# Indicators.net
KiCad netlist of a schematic drawn in Altium Designer
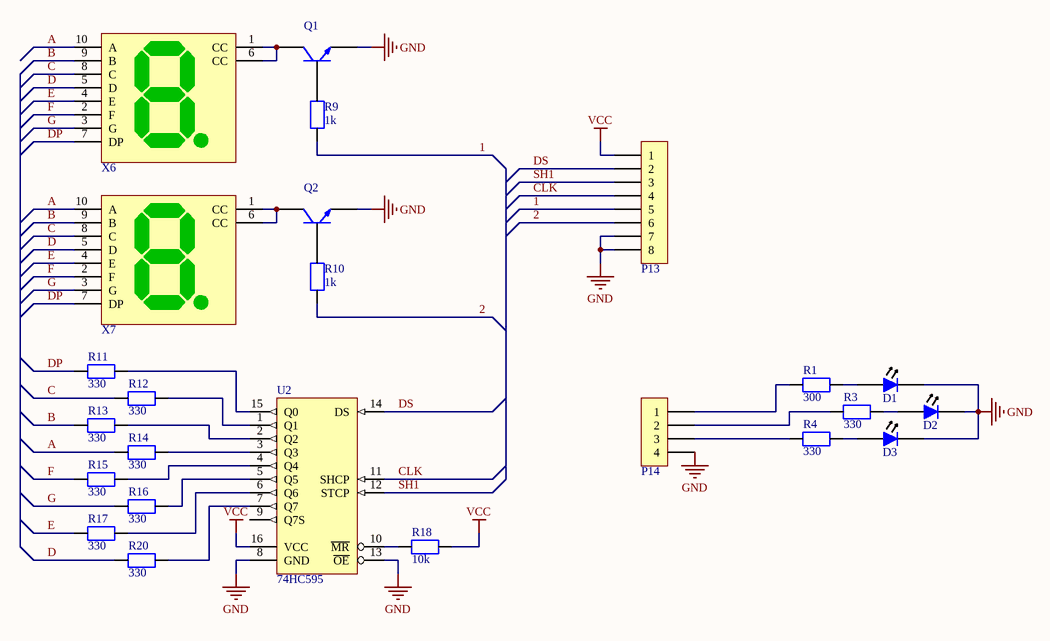
[diagram p0: Indicators.SchDoc]

(export (version "E")
  (design (tool "Eeschema 10.0.6"))
  (components
    (comp (ref "D1") (value "LED") (footprint "LED") (libsource (lib "SchLib1") (part "LED")))
    (comp (ref "D2") (value "LED") (footprint "LED") (libsource (lib "SchLib1") (part "LED")))
    (comp (ref "D3") (value "LED") (footprint "LED") (libsource (lib "SchLib1") (part "LED")))
    (comp (ref "P13")
      (value "SIL-CONN-8")
      (footprint "SIL-CONN-8-R1")
      (libsource (lib "SchLib1") (part "SIL-CONN-8"))
    )
    (comp (ref "P14")
      (value "SIL-CONN-4")
      (footprint "SIL-CONN-4-R1")
      (libsource (lib "SchLib1") (part "SIL-CONN-4"))
    )
    (comp (ref "Q1") (value "KT315") (footprint "KT315") (libsource (lib "SchLib1") (part "KT315")))
    (comp (ref "Q2") (value "KT315") (footprint "KT315") (libsource (lib "SchLib1") (part "KT315")))
    (comp (ref "R1")
      (value "300")
      (footprint "0805_Resistor")
      (fields (field (name "Comment") "Resistor"))
      (libsource (lib "SchLib1") (part "Resistor"))
    )
    (comp (ref "R3")
      (value "330")
      (footprint "0805_Resistor")
      (fields (field (name "Comment") "Resistor"))
      (libsource (lib "SchLib1") (part "Resistor"))
    )
    (comp (ref "R4")
      (value "330")
      (footprint "0805_Resistor")
      (fields (field (name "Comment") "Resistor"))
      (libsource (lib "SchLib1") (part "Resistor"))
    )
    (comp (ref "R9")
      (value "1k")
      (footprint "0805_Resistor")
      (fields (field (name "Comment") "Resistor"))
      (libsource (lib "") (part "Resistor_1"))
    )
    (comp (ref "R10")
      (value "1k")
      (footprint "0805_Resistor")
      (fields (field (name "Comment") "Resistor"))
      (libsource (lib "") (part "Resistor_1"))
    )
    (comp (ref "R11")
      (value "330")
      (footprint "0805_Resistor")
      (fields (field (name "Comment") "Resistor"))
      (libsource (lib "SchLib1") (part "Resistor"))
    )
    (comp (ref "R12")
      (value "330")
      (footprint "0805_Resistor")
      (fields (field (name "Comment") "Resistor"))
      (libsource (lib "SchLib1") (part "Resistor"))
    )
    (comp (ref "R13")
      (value "330")
      (footprint "0805_Resistor")
      (fields (field (name "Comment") "Resistor"))
      (libsource (lib "SchLib1") (part "Resistor"))
    )
    (comp (ref "R14")
      (value "330")
      (footprint "0805_Resistor")
      (fields (field (name "Comment") "Resistor"))
      (libsource (lib "SchLib1") (part "Resistor"))
    )
    (comp (ref "R15")
      (value "330")
      (footprint "0805_Resistor")
      (fields (field (name "Comment") "Resistor"))
      (libsource (lib "SchLib1") (part "Resistor"))
    )
    (comp (ref "R16")
      (value "330")
      (footprint "0805_Resistor")
      (fields (field (name "Comment") "Resistor"))
      (libsource (lib "SchLib1") (part "Resistor"))
    )
    (comp (ref "R17")
      (value "330")
      (footprint "0805_Resistor")
      (fields (field (name "Comment") "Resistor"))
      (libsource (lib "SchLib1") (part "Resistor"))
    )
    (comp (ref "R18")
      (value "10k")
      (footprint "0805_Resistor")
      (fields (field (name "Comment") "Resistor"))
      (libsource (lib "SchLib1") (part "Resistor"))
    )
    (comp (ref "R20")
      (value "330")
      (footprint "0805_Resistor")
      (fields (field (name "Comment") "Resistor"))
      (libsource (lib "SchLib1") (part "Resistor"))
    )
    (comp (ref "U2") (value "74HC595") (footprint "SOIC16") (libsource (lib "SchLib1") (part "74HC595")))
    (comp (ref "X6") (value "FYS-3912") (footprint "FYS-3916") (libsource (lib "SchLib1") (part "FYS-3912")))
    (comp (ref "X7") (value "FYS-3912") (footprint "FYS-3916") (libsource (lib "SchLib1") (part "FYS-3912")))
  )
  (nets
    (net (code "1") (name "/1") (class "Default")
      (node (ref "P13") (pin "5") (pinfunction "5_5") (pintype "passive"))
      (node (ref "R9") (pin "1") (pinfunction "1_1") (pintype "passive"))
    )
    (net (code "2") (name "/2") (class "Default")
      (node (ref "P13") (pin "6") (pinfunction "6_6") (pintype "passive"))
      (node (ref "R10") (pin "1") (pinfunction "1_1") (pintype "passive"))
    )
    (net (code "3") (name "/A") (class "Default")
      (node (ref "R14") (pin "2") (pinfunction "2_2") (pintype "passive"))
      (node (ref "X6") (pin "10") (pinfunction "A_10") (pintype "passive"))
      (node (ref "X7") (pin "10") (pinfunction "A_10") (pintype "passive"))
    )
    (net (code "4") (name "/B") (class "Default")
      (node (ref "R13") (pin "2") (pinfunction "2_2") (pintype "passive"))
      (node (ref "X6") (pin "9") (pinfunction "B_9") (pintype "passive"))
      (node (ref "X7") (pin "9") (pinfunction "B_9") (pintype "passive"))
    )
    (net (code "5") (name "/C") (class "Default")
      (node (ref "R12") (pin "2") (pinfunction "2_2") (pintype "passive"))
      (node (ref "X6") (pin "8") (pinfunction "C_8") (pintype "passive"))
      (node (ref "X7") (pin "8") (pinfunction "C_8") (pintype "passive"))
    )
    (net (code "6") (name "/CLK") (class "Default")
      (node (ref "P13") (pin "4") (pinfunction "4_4") (pintype "passive"))
      (node (ref "U2") (pin "11") (pinfunction "SHCP_11") (pintype "input"))
    )
    (net (code "7") (name "/D") (class "Default")
      (node (ref "R20") (pin "2") (pinfunction "2_2") (pintype "passive"))
      (node (ref "X6") (pin "5") (pinfunction "D_5") (pintype "passive"))
      (node (ref "X7") (pin "5") (pinfunction "D_5") (pintype "passive"))
    )
    (net (code "8") (name "/DP") (class "Default")
      (node (ref "R11") (pin "2") (pinfunction "2_2") (pintype "passive"))
      (node (ref "X6") (pin "7") (pinfunction "DP_7") (pintype "passive"))
      (node (ref "X7") (pin "7") (pinfunction "DP_7") (pintype "passive"))
    )
    (net (code "9") (name "/DS") (class "Default")
      (node (ref "P13") (pin "2") (pinfunction "2_2") (pintype "passive"))
      (node (ref "U2") (pin "14") (pinfunction "DS_14") (pintype "input"))
    )
    (net (code "10") (name "/E") (class "Default")
      (node (ref "R17") (pin "2") (pinfunction "2_2") (pintype "passive"))
      (node (ref "X6") (pin "4") (pinfunction "E_4") (pintype "passive"))
      (node (ref "X7") (pin "4") (pinfunction "E_4") (pintype "passive"))
    )
    (net (code "11") (name "/F") (class "Default")
      (node (ref "R15") (pin "2") (pinfunction "2_2") (pintype "passive"))
      (node (ref "X6") (pin "2") (pinfunction "F_2") (pintype "passive"))
      (node (ref "X7") (pin "2") (pinfunction "F_2") (pintype "passive"))
    )
    (net (code "12") (name "/G") (class "Default")
      (node (ref "R16") (pin "2") (pinfunction "2_2") (pintype "passive"))
      (node (ref "X6") (pin "3") (pinfunction "G_3") (pintype "passive"))
      (node (ref "X7") (pin "3") (pinfunction "G_3") (pintype "passive"))
    )
    (net (code "13") (name "/SH1") (class "Default")
      (node (ref "P13") (pin "3") (pinfunction "3_3") (pintype "passive"))
      (node (ref "U2") (pin "12") (pinfunction "STCP_12") (pintype "input"))
    )
    (net (code "14") (name "GND") (class "Default")
      (node (ref "D1") (pin "K") (pinfunction "K_K") (pintype "passive"))
      (node (ref "D2") (pin "K") (pinfunction "K_K") (pintype "passive"))
      (node (ref "D3") (pin "K") (pinfunction "K_K") (pintype "passive"))
      (node (ref "P13") (pin "7") (pinfunction "7_7") (pintype "passive"))
      (node (ref "P13") (pin "8") (pinfunction "8_8") (pintype "passive"))
      (node (ref "P14") (pin "4") (pinfunction "4_4") (pintype "passive"))
      (node (ref "Q1") (pin "E") (pinfunction "E_E") (pintype "passive"))
      (node (ref "Q2") (pin "E") (pinfunction "E_E") (pintype "passive"))
      (node (ref "U2") (pin "13") (pinfunction "~{OE}_13") (pintype "passive"))
      (node (ref "U2") (pin "8") (pinfunction "GND_8") (pintype "power_in"))
    )
    (net (code "15") (name "Net-(D1-PadA)") (class "Default")
      (node (ref "D1") (pin "A") (pinfunction "A_A") (pintype "passive"))
      (node (ref "R1") (pin "1") (pinfunction "1_1") (pintype "passive"))
    )
    (net (code "16") (name "Net-(D2-PadA)") (class "Default")
      (node (ref "D2") (pin "A") (pinfunction "A_A") (pintype "passive"))
      (node (ref "R3") (pin "1") (pinfunction "1_1") (pintype "passive"))
    )
    (net (code "17") (name "Net-(D3-PadA)") (class "Default")
      (node (ref "D3") (pin "A") (pinfunction "A_A") (pintype "passive"))
      (node (ref "R4") (pin "1") (pinfunction "1_1") (pintype "passive"))
    )
    (net (code "18") (name "Net-(P14-Pad1)") (class "Default")
      (node (ref "P14") (pin "1") (pinfunction "1_1") (pintype "passive"))
      (node (ref "R1") (pin "2") (pinfunction "2_2") (pintype "passive"))
    )
    (net (code "19") (name "Net-(P14-Pad2)") (class "Default")
      (node (ref "P14") (pin "2") (pinfunction "2_2") (pintype "passive"))
      (node (ref "R3") (pin "2") (pinfunction "2_2") (pintype "passive"))
    )
    (net (code "20") (name "Net-(P14-Pad3)") (class "Default")
      (node (ref "P14") (pin "3") (pinfunction "3_3") (pintype "passive"))
      (node (ref "R4") (pin "2") (pinfunction "2_2") (pintype "passive"))
    )
    (net (code "21") (name "Net-(Q1-PadB)") (class "Default")
      (node (ref "Q1") (pin "B") (pinfunction "B_B") (pintype "passive"))
      (node (ref "R9") (pin "2") (pinfunction "2_2") (pintype "passive"))
    )
    (net (code "22") (name "Net-(Q1-PadK)") (class "Default")
      (node (ref "Q1") (pin "K") (pinfunction "K_K") (pintype "passive"))
      (node (ref "X6") (pin "1") (pinfunction "CC_1") (pintype "passive"))
      (node (ref "X6") (pin "6") (pinfunction "CC_6") (pintype "passive"))
    )
    (net (code "23") (name "Net-(Q2-PadB)") (class "Default")
      (node (ref "Q2") (pin "B") (pinfunction "B_B") (pintype "passive"))
      (node (ref "R10") (pin "2") (pinfunction "2_2") (pintype "passive"))
    )
    (net (code "24") (name "Net-(Q2-PadK)") (class "Default")
      (node (ref "Q2") (pin "K") (pinfunction "K_K") (pintype "passive"))
      (node (ref "X7") (pin "1") (pinfunction "CC_1") (pintype "passive"))
      (node (ref "X7") (pin "6") (pinfunction "CC_6") (pintype "passive"))
    )
    (net (code "25") (name "Net-(U2-Q0)") (class "Default")
      (node (ref "R11") (pin "1") (pinfunction "1_1") (pintype "passive"))
      (node (ref "U2") (pin "15") (pinfunction "Q0_15") (pintype "output"))
    )
    (net (code "26") (name "Net-(U2-Q1)") (class "Default")
      (node (ref "R12") (pin "1") (pinfunction "1_1") (pintype "passive"))
      (node (ref "U2") (pin "1") (pinfunction "Q1_1") (pintype "output"))
    )
    (net (code "27") (name "Net-(U2-Q2)") (class "Default")
      (node (ref "R13") (pin "1") (pinfunction "1_1") (pintype "passive"))
      (node (ref "U2") (pin "2") (pinfunction "Q2_2") (pintype "output"))
    )
    (net (code "28") (name "Net-(U2-Q3)") (class "Default")
      (node (ref "R14") (pin "1") (pinfunction "1_1") (pintype "passive"))
      (node (ref "U2") (pin "3") (pinfunction "Q3_3") (pintype "output"))
    )
    (net (code "29") (name "Net-(U2-Q4)") (class "Default")
      (node (ref "R15") (pin "1") (pinfunction "1_1") (pintype "passive"))
      (node (ref "U2") (pin "4") (pinfunction "Q4_4") (pintype "output"))
    )
    (net (code "30") (name "Net-(U2-Q5)") (class "Default")
      (node (ref "R16") (pin "1") (pinfunction "1_1") (pintype "passive"))
      (node (ref "U2") (pin "5") (pinfunction "Q5_5") (pintype "output"))
    )
    (net (code "31") (name "Net-(U2-Q6)") (class "Default")
      (node (ref "R17") (pin "1") (pinfunction "1_1") (pintype "passive"))
      (node (ref "U2") (pin "6") (pinfunction "Q6_6") (pintype "output"))
    )
    (net (code "32") (name "Net-(U2-Q7)") (class "Default")
      (node (ref "R20") (pin "1") (pinfunction "1_1") (pintype "passive"))
      (node (ref "U2") (pin "7") (pinfunction "Q7_7") (pintype "output"))
    )
    (net (code "33") (name "Net-(U2-~{MR})") (class "Default")
      (node (ref "R18") (pin "2") (pinfunction "2_2") (pintype "passive"))
      (node (ref "U2") (pin "10") (pinfunction "~{MR}_10") (pintype "passive"))
    )
    (net (code "34") (name "VCC") (class "Default")
      (node (ref "P13") (pin "1") (pinfunction "1_1") (pintype "passive"))
      (node (ref "R18") (pin "1") (pinfunction "1_1") (pintype "passive"))
      (node (ref "U2") (pin "16") (pinfunction "VCC_16") (pintype "power_in"))
    )
    (net (code "35") (name "unconnected-(U2-Q7S-Pad9)") (class "Default")
      (node (ref "U2") (pin "9") (pinfunction "Q7S_9") (pintype "output"))
    )
  )
)
